# pixracer_serials.net
KiCad netlist of a schematic drawn in Altium Designer
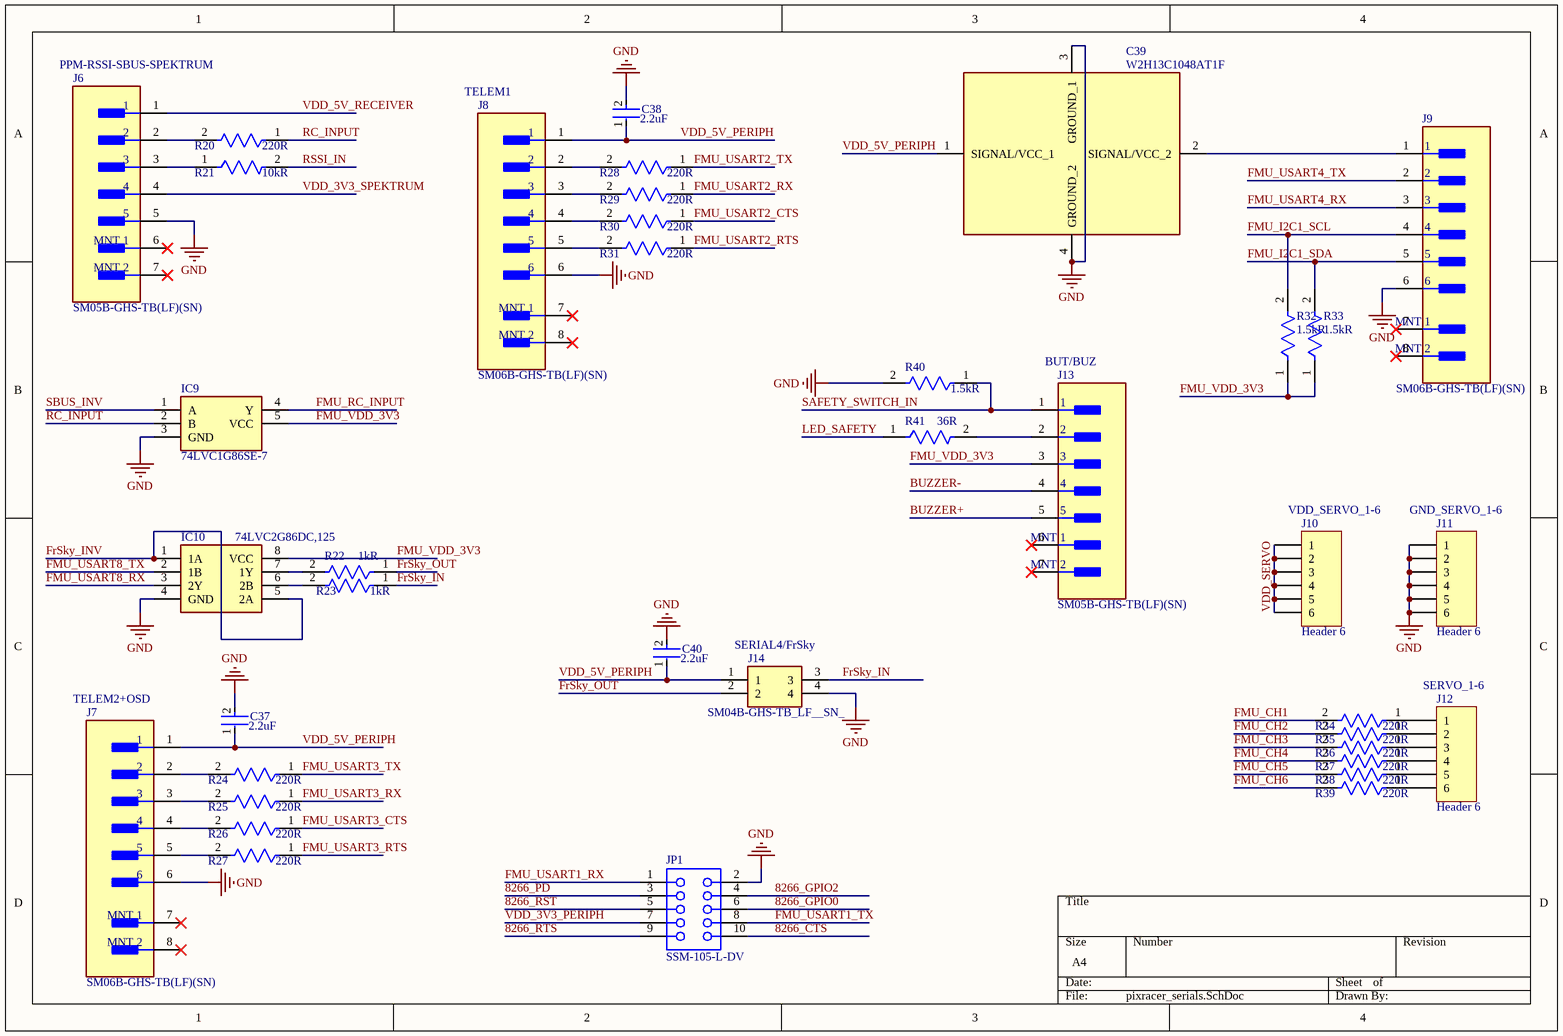
[diagram p0: pixracer_serials.SchDoc]

(export (version "E")
  (design (tool "Eeschema 10.0.6"))
  (components
    (comp (ref "C37")
      (value "C1608X7R1A225K080AC")
      (footprint "FP-C1608-080-0_1-MFG")
      (description "Multilayer Ceramic Capacitors 2.2μF ±10% 10V X7R SMD 0603")
      (fields (field (name "CAPACITANCE") "2.2uF") (field (name "TOLERANCE") "10%"))
      (libsource (lib "Altium Content Vault") (part "236180d848d6139a670b325ea6854c9"))
    )
    (comp (ref "C38")
      (value "C1608X7R1A225K080AC")
      (footprint "FP-C1608-080-0_1-MFG")
      (description "Multilayer Ceramic Capacitors 2.2μF ±10% 10V X7R SMD 0603")
      (fields (field (name "CAPACITANCE") "2.2uF") (field (name "TOLERANCE") "10%"))
      (libsource (lib "Altium Content Vault") (part "236180d848d6139a670b325ea6854c9"))
    )
    (comp (ref "C39")
      (value "W2H13C1048AT1F")
      (footprint "SamacSys:W2H13C1048AT1A")
      (description "Capacitor")
      (fields (field (name "MOUSER PART NUMBER") "581-W2H13C1048AT1F"))
      (libsource (lib "*") (part "W2H13C1048AT1F"))
    )
    (comp (ref "C40")
      (value "C1608X7R1A225K080AC")
      (footprint "FP-C1608-080-0_1-MFG")
      (description "Multilayer Ceramic Capacitors 2.2μF ±10% 10V X7R SMD 0603")
      (fields (field (name "CAPACITANCE") "2.2uF") (field (name "TOLERANCE") "10%"))
      (libsource (lib "Altium Content Vault") (part "236180d848d6139a670b325ea6854c9"))
    )
    (comp (ref "IC9")
      (value "74LVC1G86SE-7")
      (footprint "SamacSys:SOT65P210X110-5N")
      (description "Integrated Circuit")
      (fields (field (name "MOUSER PART NUMBER") "621-74LVC1G86SE-7"))
      (libsource (lib "*") (part "74LVC1G86SE-7"))
    )
    (comp (ref "IC10")
      (value "74LVC2G86DC,125")
      (footprint "SamacSys:SOP50P310X100-8N")
      (description "Integrated Circuit")
      (fields (field (name "MOUSER PART NUMBER") "771-LVC2G86DC125"))
      (libsource (lib "*") (part "74LVC2G86DC,125"))
    )
    (comp (ref "J6")
      (value "SM05B-GHS-TB(LF)(SN)")
      (footprint "FP-SM05B-GHS-TB_LF_SN-MFG")
      (description "CONN HEADER SMD R/A 5POS 1.25MM")
      (libsource (lib "") (part "8ab9848ea90b119fa28a5ddc5abf419_1"))
    )
    (comp (ref "J7")
      (value "SM06B-GHS-TB(LF)(SN)")
      (footprint "FP-SM06B-GHS-TB_LF_SN-MFG")
      (description "CONN HEADER SMD R/A 6POS 1.25MM")
      (libsource (lib "Altium Content Vault") (part "ed24c53d9ba001d1a2a686240a95171"))
    )
    (comp (ref "J8")
      (value "SM06B-GHS-TB(LF)(SN)")
      (footprint "FP-SM06B-GHS-TB_LF_SN-MFG")
      (description "CONN HEADER SMD R/A 6POS 1.25MM")
      (libsource (lib "Altium Content Vault") (part "ed24c53d9ba001d1a2a686240a95171"))
    )
    (comp (ref "J9")
      (value "SM06B-GHS-TB(LF)(SN)")
      (footprint "FP-SM06B-GHS-TB_LF_SN-MFG")
      (description "CONN HEADER SMD R/A 6POS 1.25MM")
      (libsource (lib "") (part "ed24c53d9ba001d1a2a686240a95171_1"))
    )
    (comp (ref "J10")
      (value "Header 6")
      (footprint "HDR1X6")
      (description "Header, 6-Pin")
      (fields (field (name "PUBLISHER") "Altium Limited"))
      (libsource (lib "Miscellaneous Connectors") (part "Header 6"))
    )
    (comp (ref "J11")
      (value "Header 6")
      (footprint "HDR1X6")
      (description "Header, 6-Pin")
      (fields (field (name "PUBLISHER") "Altium Limited"))
      (libsource (lib "Miscellaneous Connectors") (part "Header 6"))
    )
    (comp (ref "J12")
      (value "Header 6")
      (footprint "HDR1X6")
      (description "Header, 6-Pin")
      (fields (field (name "PUBLISHER") "Altium Limited"))
      (libsource (lib "Miscellaneous Connectors") (part "Header 6"))
    )
    (comp (ref "J13")
      (value "SM05B-GHS-TB(LF)(SN)")
      (footprint "FP-SM05B-GHS-TB_LF_SN-MFG")
      (description "CONN HEADER SMD R/A 5POS 1.25MM")
      (libsource (lib "Altium Content Vault") (part "8ab9848ea90b119fa28a5ddc5abf419"))
    )
    (comp (ref "J14")
      (value "SM04B-GHS-TB_LF__SN_")
      (footprint "SamacSys:SM04B-GHS-TB")
      (description "Connector")
      (fields (field (name "MANUFACTURER_PART_NUMBER") "SM04B-GHS-TB(LF)(SN)"))
      (libsource (lib "*") (part "SM04B-GHS-TB_LF__SN_"))
    )
    (comp (ref "JP1")
      (value "SSM-105-L-DV")
      (footprint "SMTC-SSM-105-X-DV")
      (fields (field (name "MANUFACTURER") "Samtec"))
      (libsource (lib "Altium Content Vault") (part "SMTC-SSM-105-X-DV"))
    )
    (comp (ref "R20")
      (value "CRCW0603220RFKEB")
      (footprint "FP-CRCW0603-e3-MFG")
      (description "RES Thick Film, 220Ω, 1%, 0.1W, 100ppm/°C, 0603")
      (fields (field (name "TOLERANCE") "1%") (field (name "RESISTANCE") "220R"))
      (libsource (lib "Altium Content Vault") (part "1029c3af85768c4190bb7ad29bc67b5"))
    )
    (comp (ref "R21")
      (value "ERJ-3GEYJ103V")
      (footprint "FP-ERJ3G-IPC_C")
      (description "RES SMD 10K OHM 5% 1/10W 0603")
      (fields (field (name "TOLERANCE") "5%") (field (name "RESISTANCE") "10kR"))
      (libsource (lib "Altium Content Vault") (part "1029c3af85768c4190bb7ad29bc67b5"))
    )
    (comp (ref "R22")
      (value "RC1608J102CS")
      (footprint "FP-RC1608-IPC_A")
      (description "Res Thick Film 0603 1kΩ 5% 0.1W ±100ppm/°C Molded SMD T/R")
      (fields (field (name "RESISTANCE") "1kR") (field (name "TOLERANCE") "5%"))
      (libsource (lib "Altium Content Vault") (part "1029c3af85768c4190bb7ad29bc67b5"))
    )
    (comp (ref "R23")
      (value "RC1608J102CS")
      (footprint "FP-RC1608-IPC_A")
      (description "Res Thick Film 0603 1kΩ 5% 0.1W ±100ppm/°C Molded SMD T/R")
      (fields (field (name "RESISTANCE") "1kR") (field (name "TOLERANCE") "5%"))
      (libsource (lib "Altium Content Vault") (part "1029c3af85768c4190bb7ad29bc67b5"))
    )
    (comp (ref "R24")
      (value "CRCW0603220RFKEB")
      (footprint "FP-CRCW0603-e3-MFG")
      (description "RES Thick Film, 220Ω, 1%, 0.1W, 100ppm/°C, 0603")
      (fields (field (name "TOLERANCE") "1%") (field (name "RESISTANCE") "220R"))
      (libsource (lib "Altium Content Vault") (part "1029c3af85768c4190bb7ad29bc67b5"))
    )
    (comp (ref "R25")
      (value "CRCW0603220RFKEB")
      (footprint "FP-CRCW0603-e3-MFG")
      (description "RES Thick Film, 220Ω, 1%, 0.1W, 100ppm/°C, 0603")
      (fields (field (name "TOLERANCE") "1%") (field (name "RESISTANCE") "220R"))
      (libsource (lib "Altium Content Vault") (part "1029c3af85768c4190bb7ad29bc67b5"))
    )
    (comp (ref "R26")
      (value "CRCW0603220RFKEB")
      (footprint "FP-CRCW0603-e3-MFG")
      (description "RES Thick Film, 220Ω, 1%, 0.1W, 100ppm/°C, 0603")
      (fields (field (name "TOLERANCE") "1%") (field (name "RESISTANCE") "220R"))
      (libsource (lib "Altium Content Vault") (part "1029c3af85768c4190bb7ad29bc67b5"))
    )
    (comp (ref "R27")
      (value "CRCW0603220RFKEB")
      (footprint "FP-CRCW0603-e3-MFG")
      (description "RES Thick Film, 220Ω, 1%, 0.1W, 100ppm/°C, 0603")
      (fields (field (name "TOLERANCE") "1%") (field (name "RESISTANCE") "220R"))
      (libsource (lib "Altium Content Vault") (part "1029c3af85768c4190bb7ad29bc67b5"))
    )
    (comp (ref "R28")
      (value "CRCW0603220RFKEB")
      (footprint "FP-CRCW0603-e3-MFG")
      (description "RES Thick Film, 220Ω, 1%, 0.1W, 100ppm/°C, 0603")
      (fields (field (name "TOLERANCE") "1%") (field (name "RESISTANCE") "220R"))
      (libsource (lib "Altium Content Vault") (part "1029c3af85768c4190bb7ad29bc67b5"))
    )
    (comp (ref "R29")
      (value "CRCW0603220RFKEB")
      (footprint "FP-CRCW0603-e3-MFG")
      (description "RES Thick Film, 220Ω, 1%, 0.1W, 100ppm/°C, 0603")
      (fields (field (name "TOLERANCE") "1%") (field (name "RESISTANCE") "220R"))
      (libsource (lib "Altium Content Vault") (part "1029c3af85768c4190bb7ad29bc67b5"))
    )
    (comp (ref "R30")
      (value "CRCW0603220RFKEB")
      (footprint "FP-CRCW0603-e3-MFG")
      (description "RES Thick Film, 220Ω, 1%, 0.1W, 100ppm/°C, 0603")
      (fields (field (name "TOLERANCE") "1%") (field (name "RESISTANCE") "220R"))
      (libsource (lib "Altium Content Vault") (part "1029c3af85768c4190bb7ad29bc67b5"))
    )
    (comp (ref "R31")
      (value "CRCW0603220RFKEB")
      (footprint "FP-CRCW0603-e3-MFG")
      (description "RES Thick Film, 220Ω, 1%, 0.1W, 100ppm/°C, 0603")
      (fields (field (name "TOLERANCE") "1%") (field (name "RESISTANCE") "220R"))
      (libsource (lib "Altium Content Vault") (part "1029c3af85768c4190bb7ad29bc67b5"))
    )
    (comp (ref "R32")
      (value "1.5kR")
      (footprint "FP-CPF0603-MFG")
      (description "RES SMD 1.5KΩ 0.1% 1/16W 0603")
      (fields
        (field (name "MANUFACTURER PART NUMBER") "CPF0603B1K5E1")
        (field (name "OCTOPART") "https://octopart.com/cpf0603b1k5e1-te+connectivity-9539421")
      )
      (libsource (lib "Altium Content Vault") (part "1029c3af85768c4190bb7ad29bc67b5"))
    )
    (comp (ref "R33")
      (value "1.5kR")
      (footprint "FP-CPF0603-MFG")
      (description "RES SMD 1.5KΩ 0.1% 1/16W 0603")
      (fields
        (field (name "MANUFACTURER PART NUMBER") "CPF0603B1K5E1")
        (field (name "OCTOPART") "https://octopart.com/cpf0603b1k5e1-te+connectivity-9539421")
      )
      (libsource (lib "Altium Content Vault") (part "1029c3af85768c4190bb7ad29bc67b5"))
    )
    (comp (ref "R34")
      (value "CRCW0603220RFKEB")
      (footprint "FP-CRCW0603-e3-MFG")
      (description "RES Thick Film, 220Ω, 1%, 0.1W, 100ppm/°C, 0603")
      (fields (field (name "TOLERANCE") "1%") (field (name "RESISTANCE") "220R"))
      (libsource (lib "Altium Content Vault") (part "1029c3af85768c4190bb7ad29bc67b5"))
    )
    (comp (ref "R35")
      (value "CRCW0603220RFKEB")
      (footprint "FP-CRCW0603-e3-MFG")
      (description "RES Thick Film, 220Ω, 1%, 0.1W, 100ppm/°C, 0603")
      (fields (field (name "TOLERANCE") "1%") (field (name "RESISTANCE") "220R"))
      (libsource (lib "Altium Content Vault") (part "1029c3af85768c4190bb7ad29bc67b5"))
    )
    (comp (ref "R36")
      (value "CRCW0603220RFKEB")
      (footprint "FP-CRCW0603-e3-MFG")
      (description "RES Thick Film, 220Ω, 1%, 0.1W, 100ppm/°C, 0603")
      (fields (field (name "TOLERANCE") "1%") (field (name "RESISTANCE") "220R"))
      (libsource (lib "Altium Content Vault") (part "1029c3af85768c4190bb7ad29bc67b5"))
    )
    (comp (ref "R37")
      (value "CRCW0603220RFKEB")
      (footprint "FP-CRCW0603-e3-MFG")
      (description "RES Thick Film, 220Ω, 1%, 0.1W, 100ppm/°C, 0603")
      (fields (field (name "TOLERANCE") "1%") (field (name "RESISTANCE") "220R"))
      (libsource (lib "Altium Content Vault") (part "1029c3af85768c4190bb7ad29bc67b5"))
    )
    (comp (ref "R38")
      (value "CRCW0603220RFKEB")
      (footprint "FP-CRCW0603-e3-MFG")
      (description "RES Thick Film, 220Ω, 1%, 0.1W, 100ppm/°C, 0603")
      (fields (field (name "TOLERANCE") "1%") (field (name "RESISTANCE") "220R"))
      (libsource (lib "Altium Content Vault") (part "1029c3af85768c4190bb7ad29bc67b5"))
    )
    (comp (ref "R39")
      (value "CRCW0603220RFKEB")
      (footprint "FP-CRCW0603-e3-MFG")
      (description "RES Thick Film, 220Ω, 1%, 0.1W, 100ppm/°C, 0603")
      (fields (field (name "TOLERANCE") "1%") (field (name "RESISTANCE") "220R"))
      (libsource (lib "Altium Content Vault") (part "1029c3af85768c4190bb7ad29bc67b5"))
    )
    (comp (ref "R40")
      (value "MCR03EZPFX1501")
      (footprint "FP-MCR03-IPC_A")
      (description "Thick Film Chip Resistor, 0603, 1.5kΩ, 1%, 100ppm/°C, 0.1W, 50V")
      (fields (field (name "RESISTANCE") "1.5kR") (field (name "TOLERANCE") "1%"))
      (libsource (lib "Altium Content Vault") (part "1029c3af85768c4190bb7ad29bc67b5"))
    )
    (comp (ref "R41")
      (value "CRCW060336R0JNEA")
      (footprint "FP-CRCW0603-e3-IPC_B")
      (description "RES Thick Film, 36Ω, 5%, 0.1W, 200ppm/°C, 0603")
      (fields (field (name "RESISTANCE") "36R") (field (name "TOLERANCE") "5%"))
      (libsource (lib "Altium Content Vault") (part "1029c3af85768c4190bb7ad29bc67b5"))
    )
  )
  (nets
    (net (code "1") (name "/8266_CTS") (class "Default")
      (node (ref "JP1") (pin "10") (pinfunction "10_10") (pintype "passive"))
    )
    (net (code "2") (name "/8266_GPIO0") (class "Default")
      (node (ref "JP1") (pin "6") (pinfunction "6_6") (pintype "passive"))
    )
    (net (code "3") (name "/8266_GPIO2") (class "Default")
      (node (ref "JP1") (pin "4") (pinfunction "4_4") (pintype "passive"))
    )
    (net (code "4") (name "/8266_PD") (class "Default")
      (node (ref "JP1") (pin "3") (pinfunction "3_3") (pintype "passive"))
    )
    (net (code "5") (name "/8266_RST") (class "Default")
      (node (ref "JP1") (pin "5") (pinfunction "5_5") (pintype "passive"))
    )
    (net (code "6") (name "/8266_RTS") (class "Default")
      (node (ref "JP1") (pin "9") (pinfunction "9_9") (pintype "passive"))
    )
    (net (code "7") (name "/BUZZER+") (class "Default")
      (node (ref "J13") (pin "5") (pinfunction "5_5") (pintype "passive"))
    )
    (net (code "8") (name "/BUZZER-") (class "Default")
      (node (ref "J13") (pin "4") (pinfunction "4_4") (pintype "passive"))
    )
    (net (code "9") (name "/FMU_CH1") (class "Default")
      (node (ref "R34") (pin "2") (pinfunction "2_2") (pintype "passive"))
    )
    (net (code "10") (name "/FMU_CH2") (class "Default")
      (node (ref "R35") (pin "2") (pinfunction "2_2") (pintype "passive"))
    )
    (net (code "11") (name "/FMU_CH3") (class "Default")
      (node (ref "R36") (pin "2") (pinfunction "2_2") (pintype "passive"))
    )
    (net (code "12") (name "/FMU_CH4") (class "Default")
      (node (ref "R37") (pin "2") (pinfunction "2_2") (pintype "passive"))
    )
    (net (code "13") (name "/FMU_CH5") (class "Default")
      (node (ref "R38") (pin "2") (pinfunction "2_2") (pintype "passive"))
    )
    (net (code "14") (name "/FMU_CH6") (class "Default")
      (node (ref "R39") (pin "2") (pinfunction "2_2") (pintype "passive"))
    )
    (net (code "15") (name "/FMU_I2C1_SCL") (class "Default")
      (node (ref "J9") (pin "4") (pinfunction "4_4") (pintype "passive"))
      (node (ref "R32") (pin "2") (pinfunction "2_2") (pintype "passive"))
    )
    (net (code "16") (name "/FMU_I2C1_SDA") (class "Default")
      (node (ref "J9") (pin "5") (pinfunction "5_5") (pintype "passive"))
      (node (ref "R33") (pin "2") (pinfunction "2_2") (pintype "passive"))
    )
    (net (code "17") (name "/FMU_RC_INPUT") (class "Default")
      (node (ref "IC9") (pin "4") (pinfunction "Y_4") (pintype "passive"))
    )
    (net (code "18") (name "/FMU_USART1_RX") (class "Default")
      (node (ref "JP1") (pin "1") (pinfunction "1_1") (pintype "passive"))
    )
    (net (code "19") (name "/FMU_USART1_TX") (class "Default")
      (node (ref "JP1") (pin "8") (pinfunction "8_8") (pintype "passive"))
    )
    (net (code "20") (name "/FMU_USART2_CTS") (class "Default")
      (node (ref "R30") (pin "1") (pinfunction "1_1") (pintype "passive"))
    )
    (net (code "21") (name "/FMU_USART2_RTS") (class "Default")
      (node (ref "R31") (pin "1") (pinfunction "1_1") (pintype "passive"))
    )
    (net (code "22") (name "/FMU_USART2_RX") (class "Default")
      (node (ref "R29") (pin "1") (pinfunction "1_1") (pintype "passive"))
    )
    (net (code "23") (name "/FMU_USART2_TX") (class "Default")
      (node (ref "R28") (pin "1") (pinfunction "1_1") (pintype "passive"))
    )
    (net (code "24") (name "/FMU_USART3_CTS") (class "Default")
      (node (ref "R26") (pin "1") (pinfunction "1_1") (pintype "passive"))
    )
    (net (code "25") (name "/FMU_USART3_RTS") (class "Default")
      (node (ref "R27") (pin "1") (pinfunction "1_1") (pintype "passive"))
    )
    (net (code "26") (name "/FMU_USART3_RX") (class "Default")
      (node (ref "R25") (pin "1") (pinfunction "1_1") (pintype "passive"))
    )
    (net (code "27") (name "/FMU_USART3_TX") (class "Default")
      (node (ref "R24") (pin "1") (pinfunction "1_1") (pintype "passive"))
    )
    (net (code "28") (name "/FMU_USART4_RX") (class "Default")
      (node (ref "J9") (pin "3") (pinfunction "3_3") (pintype "passive"))
    )
    (net (code "29") (name "/FMU_USART4_TX") (class "Default")
      (node (ref "J9") (pin "2") (pinfunction "2_2") (pintype "passive"))
    )
    (net (code "30") (name "/FMU_USART8_RX") (class "Default")
      (node (ref "IC10") (pin "3") (pinfunction "2Y_3") (pintype "passive"))
    )
    (net (code "31") (name "/FMU_USART8_TX") (class "Default")
      (node (ref "IC10") (pin "2") (pinfunction "1B_2") (pintype "passive"))
    )
    (net (code "32") (name "/FMU_VDD_3V3") (class "Default")
      (node (ref "IC10") (pin "8") (pinfunction "VCC_8") (pintype "passive"))
      (node (ref "IC9") (pin "5") (pinfunction "VCC_5") (pintype "passive"))
      (node (ref "J13") (pin "3") (pinfunction "3_3") (pintype "passive"))
      (node (ref "R32") (pin "1") (pinfunction "1_1") (pintype "passive"))
      (node (ref "R33") (pin "1") (pinfunction "1_1") (pintype "passive"))
    )
    (net (code "33") (name "/FrSky_IN") (class "Default")
      (node (ref "J14") (pin "3") (pinfunction "3_3") (pintype "passive"))
      (node (ref "R23") (pin "1") (pinfunction "1_1") (pintype "passive"))
    )
    (net (code "34") (name "/FrSky_INV") (class "Default")
      (node (ref "IC10") (pin "1") (pinfunction "1A_1") (pintype "passive"))
      (node (ref "IC10") (pin "5") (pinfunction "2A_5") (pintype "passive"))
    )
    (net (code "35") (name "/FrSky_OUT") (class "Default")
      (node (ref "J14") (pin "2") (pinfunction "2_2") (pintype "passive"))
      (node (ref "R22") (pin "1") (pinfunction "1_1") (pintype "passive"))
    )
    (net (code "36") (name "/LED_SAFETY") (class "Default")
      (node (ref "R41") (pin "1") (pinfunction "1_1") (pintype "passive"))
    )
    (net (code "37") (name "/RC_INPUT") (class "Default")
      (node (ref "IC9") (pin "2") (pinfunction "B_2") (pintype "passive"))
      (node (ref "R20") (pin "1") (pinfunction "1_1") (pintype "passive"))
    )
    (net (code "38") (name "/RSSI_IN") (class "Default")
      (node (ref "R21") (pin "2") (pinfunction "2_2") (pintype "passive"))
    )
    (net (code "39") (name "/SAFETY_SWITCH_IN") (class "Default")
      (node (ref "J13") (pin "1") (pinfunction "1_1") (pintype "passive"))
      (node (ref "R40") (pin "1") (pinfunction "1_1") (pintype "passive"))
    )
    (net (code "40") (name "/SBUS_INV") (class "Default")
      (node (ref "IC9") (pin "1") (pinfunction "A_1") (pintype "passive"))
    )
    (net (code "41") (name "/VDD_3V3_PERIPH") (class "Default")
      (node (ref "JP1") (pin "7") (pinfunction "7_7") (pintype "passive"))
    )
    (net (code "42") (name "/VDD_3V3_SPEKTRUM") (class "Default")
      (node (ref "J6") (pin "4") (pinfunction "4_4") (pintype "passive"))
    )
    (net (code "43") (name "/VDD_5V_PERIPH") (class "Default")
      (node (ref "C37") (pin "1") (pinfunction "1_1") (pintype "passive"))
      (node (ref "C38") (pin "1") (pinfunction "1_1") (pintype "passive"))
      (node (ref "C39") (pin "1") (pinfunction "SIGNAL/VCC_1_1") (pintype "passive"))
      (node (ref "C40") (pin "1") (pinfunction "1_1") (pintype "passive"))
      (node (ref "J14") (pin "1") (pinfunction "1_1") (pintype "passive"))
      (node (ref "J7") (pin "1") (pinfunction "1_1") (pintype "passive"))
      (node (ref "J8") (pin "1") (pinfunction "1_1") (pintype "passive"))
    )
    (net (code "44") (name "/VDD_5V_RECEIVER") (class "Default")
      (node (ref "J6") (pin "1") (pinfunction "1_1") (pintype "passive"))
    )
    (net (code "45") (name "/VDD_SERVO") (class "Default")
      (node (ref "J10") (pin "1") (pinfunction "1_1") (pintype "passive"))
      (node (ref "J10") (pin "2") (pinfunction "2_2") (pintype "passive"))
      (node (ref "J10") (pin "3") (pinfunction "3_3") (pintype "passive"))
      (node (ref "J10") (pin "4") (pinfunction "4_4") (pintype "passive"))
      (node (ref "J10") (pin "5") (pinfunction "5_5") (pintype "passive"))
      (node (ref "J10") (pin "6") (pinfunction "6_6") (pintype "passive"))
    )
    (net (code "46") (name "GND") (class "Default")
      (node (ref "C37") (pin "2") (pinfunction "2_2") (pintype "passive"))
      (node (ref "C38") (pin "2") (pinfunction "2_2") (pintype "passive"))
      (node (ref "C39") (pin "3") (pinfunction "GROUND_1_3") (pintype "passive"))
      (node (ref "C39") (pin "4") (pinfunction "GROUND_2_4") (pintype "passive"))
      (node (ref "C40") (pin "2") (pinfunction "2_2") (pintype "passive"))
      (node (ref "IC10") (pin "4") (pinfunction "GND_4") (pintype "passive"))
      (node (ref "IC9") (pin "3") (pinfunction "GND_3") (pintype "passive"))
      (node (ref "J11") (pin "1") (pinfunction "1_1") (pintype "passive"))
      (node (ref "J11") (pin "2") (pinfunction "2_2") (pintype "passive"))
      (node (ref "J11") (pin "3") (pinfunction "3_3") (pintype "passive"))
      (node (ref "J11") (pin "4") (pinfunction "4_4") (pintype "passive"))
      (node (ref "J11") (pin "5") (pinfunction "5_5") (pintype "passive"))
      (node (ref "J11") (pin "6") (pinfunction "6_6") (pintype "passive"))
      (node (ref "J14") (pin "4") (pinfunction "4_4") (pintype "passive"))
      (node (ref "J6") (pin "5") (pinfunction "5_5") (pintype "passive"))
      (node (ref "J7") (pin "6") (pinfunction "6_6") (pintype "passive"))
      (node (ref "J8") (pin "6") (pinfunction "6_6") (pintype "passive"))
      (node (ref "J9") (pin "6") (pinfunction "6_6") (pintype "passive"))
      (node (ref "JP1") (pin "2") (pinfunction "2_2") (pintype "passive"))
      (node (ref "R40") (pin "2") (pinfunction "2_2") (pintype "passive"))
    )
    (net (code "47") (name "Net-(C39-SIGNAL{slash}VCC_2)") (class "Default")
      (node (ref "C39") (pin "2") (pinfunction "SIGNAL/VCC_2_2") (pintype "passive"))
      (node (ref "J9") (pin "1") (pinfunction "1_1") (pintype "passive"))
    )
    (net (code "48") (name "Net-(IC10-1Y)") (class "Default")
      (node (ref "IC10") (pin "7") (pinfunction "1Y_7") (pintype "passive"))
      (node (ref "R22") (pin "2") (pinfunction "2_2") (pintype "passive"))
    )
    (net (code "49") (name "Net-(IC10-2B)") (class "Default")
      (node (ref "IC10") (pin "6") (pinfunction "2B_6") (pintype "passive"))
      (node (ref "R23") (pin "2") (pinfunction "2_2") (pintype "passive"))
    )
    (net (code "50") (name "Net-(J6-Pad2)") (class "Default")
      (node (ref "J6") (pin "2") (pinfunction "2_2") (pintype "passive"))
      (node (ref "R20") (pin "2") (pinfunction "2_2") (pintype "passive"))
    )
    (net (code "51") (name "Net-(J6-Pad3)") (class "Default")
      (node (ref "J6") (pin "3") (pinfunction "3_3") (pintype "passive"))
      (node (ref "R21") (pin "1") (pinfunction "1_1") (pintype "passive"))
    )
    (net (code "52") (name "Net-(J7-Pad2)") (class "Default")
      (node (ref "J7") (pin "2") (pinfunction "2_2") (pintype "passive"))
      (node (ref "R24") (pin "2") (pinfunction "2_2") (pintype "passive"))
    )
    (net (code "53") (name "Net-(J7-Pad3)") (class "Default")
      (node (ref "J7") (pin "3") (pinfunction "3_3") (pintype "passive"))
      (node (ref "R25") (pin "2") (pinfunction "2_2") (pintype "passive"))
    )
    (net (code "54") (name "Net-(J7-Pad4)") (class "Default")
      (node (ref "J7") (pin "4") (pinfunction "4_4") (pintype "passive"))
      (node (ref "R26") (pin "2") (pinfunction "2_2") (pintype "passive"))
    )
    (net (code "55") (name "Net-(J7-Pad5)") (class "Default")
      (node (ref "J7") (pin "5") (pinfunction "5_5") (pintype "passive"))
      (node (ref "R27") (pin "2") (pinfunction "2_2") (pintype "passive"))
    )
    (net (code "56") (name "Net-(J8-Pad2)") (class "Default")
      (node (ref "J8") (pin "2") (pinfunction "2_2") (pintype "passive"))
      (node (ref "R28") (pin "2") (pinfunction "2_2") (pintype "passive"))
    )
    (net (code "57") (name "Net-(J8-Pad3)") (class "Default")
      (node (ref "J8") (pin "3") (pinfunction "3_3") (pintype "passive"))
      (node (ref "R29") (pin "2") (pinfunction "2_2") (pintype "passive"))
    )
    (net (code "58") (name "Net-(J8-Pad4)") (class "Default")
      (node (ref "J8") (pin "4") (pinfunction "4_4") (pintype "passive"))
      (node (ref "R30") (pin "2") (pinfunction "2_2") (pintype "passive"))
    )
    (net (code "59") (name "Net-(J8-Pad5)") (class "Default")
      (node (ref "J8") (pin "5") (pinfunction "5_5") (pintype "passive"))
      (node (ref "R31") (pin "2") (pinfunction "2_2") (pintype "passive"))
    )
    (net (code "60") (name "Net-(J12-Pad1)") (class "Default")
      (node (ref "J12") (pin "1") (pinfunction "1_1") (pintype "passive"))
      (node (ref "R34") (pin "1") (pinfunction "1_1") (pintype "passive"))
    )
    (net (code "61") (name "Net-(J12-Pad2)") (class "Default")
      (node (ref "J12") (pin "2") (pinfunction "2_2") (pintype "passive"))
      (node (ref "R35") (pin "1") (pinfunction "1_1") (pintype "passive"))
    )
    (net (code "62") (name "Net-(J12-Pad3)") (class "Default")
      (node (ref "J12") (pin "3") (pinfunction "3_3") (pintype "passive"))
      (node (ref "R36") (pin "1") (pinfunction "1_1") (pintype "passive"))
    )
    (net (code "63") (name "Net-(J12-Pad4)") (class "Default")
      (node (ref "J12") (pin "4") (pinfunction "4_4") (pintype "passive"))
      (node (ref "R37") (pin "1") (pinfunction "1_1") (pintype "passive"))
    )
    (net (code "64") (name "Net-(J12-Pad5)") (class "Default")
      (node (ref "J12") (pin "5") (pinfunction "5_5") (pintype "passive"))
      (node (ref "R38") (pin "1") (pinfunction "1_1") (pintype "passive"))
    )
    (net (code "65") (name "Net-(J12-Pad6)") (class "Default")
      (node (ref "J12") (pin "6") (pinfunction "6_6") (pintype "passive"))
      (node (ref "R39") (pin "1") (pinfunction "1_1") (pintype "passive"))
    )
    (net (code "66") (name "Net-(J13-Pad2)") (class "Default")
      (node (ref "J13") (pin "2") (pinfunction "2_2") (pintype "passive"))
      (node (ref "R41") (pin "2") (pinfunction "2_2") (pintype "passive"))
    )
    (net (code "67") (name "unconnected-(J6-MNT_1-Pad6)") (class "Default")
      (node (ref "J6") (pin "6") (pinfunction "MNT_1_6") (pintype "passive+no_connect"))
    )
    (net (code "68") (name "unconnected-(J6-MNT_2-Pad7)") (class "Default")
      (node (ref "J6") (pin "7") (pinfunction "MNT_2_7") (pintype "passive+no_connect"))
    )
    (net (code "69") (name "unconnected-(J7-MNT_1-Pad7)") (class "Default")
      (node (ref "J7") (pin "7") (pinfunction "MNT_1_7") (pintype "passive+no_connect"))
    )
    (net (code "70") (name "unconnected-(J7-MNT_2-Pad8)") (class "Default")
      (node (ref "J7") (pin "8") (pinfunction "MNT_2_8") (pintype "passive+no_connect"))
    )
    (net (code "71") (name "unconnected-(J8-MNT_1-Pad7)") (class "Default")
      (node (ref "J8") (pin "7") (pinfunction "MNT_1_7") (pintype "passive+no_connect"))
    )
    (net (code "72") (name "unconnected-(J8-MNT_2-Pad8)") (class "Default")
      (node (ref "J8") (pin "8") (pinfunction "MNT_2_8") (pintype "passive+no_connect"))
    )
    (net (code "73") (name "unconnected-(J9-MNT_1-Pad7)") (class "Default")
      (node (ref "J9") (pin "7") (pinfunction "MNT_1_7") (pintype "passive+no_connect"))
    )
    (net (code "74") (name "unconnected-(J9-MNT_2-Pad8)") (class "Default")
      (node (ref "J9") (pin "8") (pinfunction "MNT_2_8") (pintype "passive+no_connect"))
    )
    (net (code "75") (name "unconnected-(J13-MNT_1-Pad6)") (class "Default")
      (node (ref "J13") (pin "6") (pinfunction "MNT_1_6") (pintype "passive+no_connect"))
    )
    (net (code "76") (name "unconnected-(J13-MNT_2-Pad7)") (class "Default")
      (node (ref "J13") (pin "7") (pinfunction "MNT_2_7") (pintype "passive+no_connect"))
    )
  )
)
